# ESP_PROTO1_0.net
KiCad netlist of a schematic drawn in EAGLE
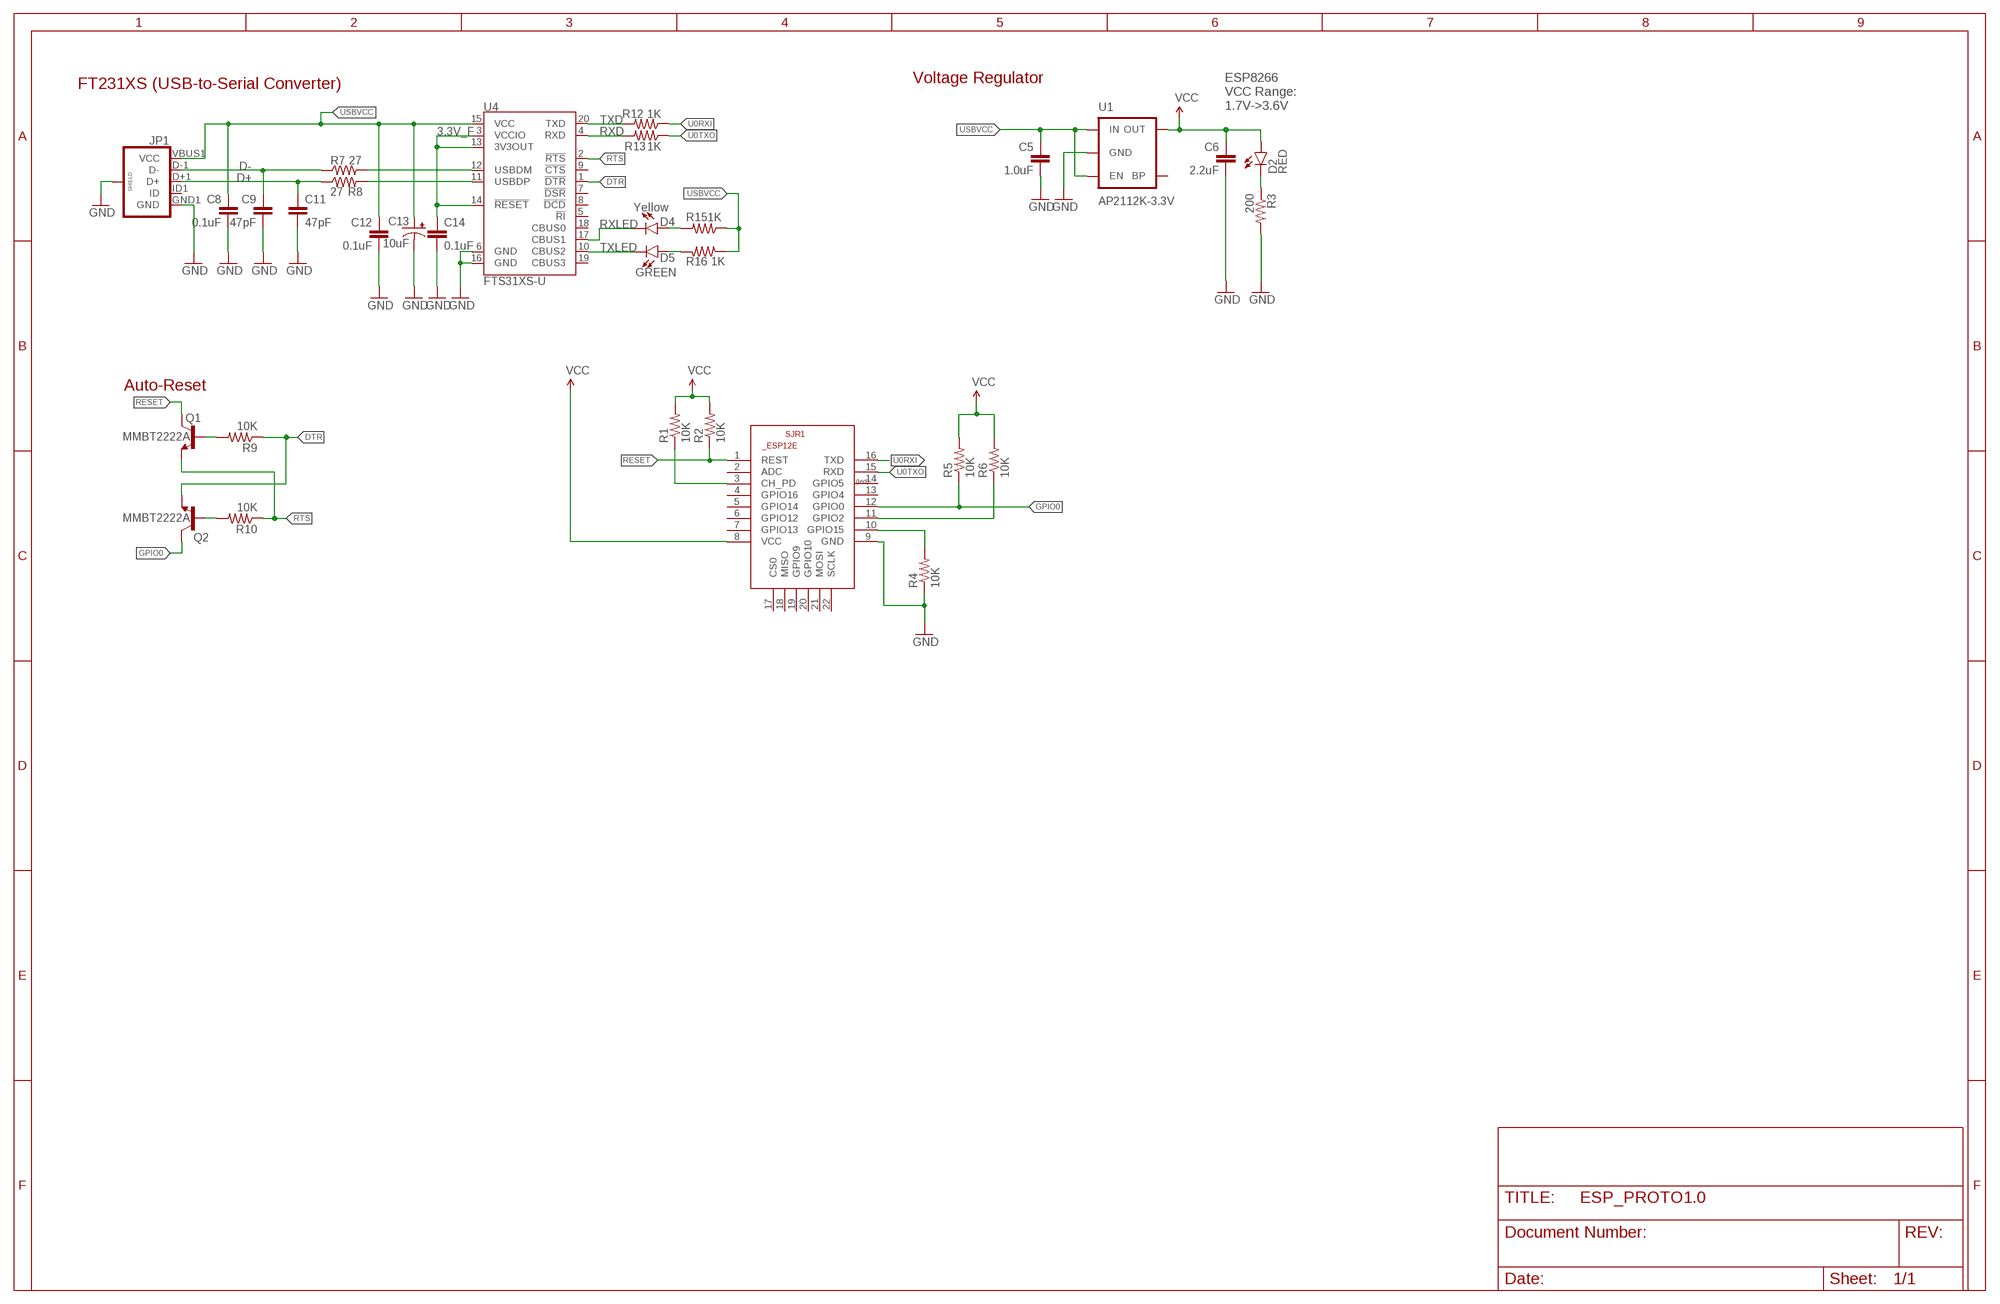
[diagram p0: schematic, sheet 1]

(export (version "E")
  (design (tool "Eeschema 10.0.6"))
  (components
    (comp (ref "C5")
      (value "1.0uF")
      (footprint "eagle-import:0805")
      (libsource (lib "eagle-import") (part "1.0UF-25V-+80/-20(0805)"))
    )
    (comp (ref "C6")
      (value "2.2uF")
      (footprint "eagle-import:0603-CAP")
      (libsource (lib "eagle-import") (part "2.2UF-10V-20%(0603)"))
    )
    (comp (ref "C8")
      (value "0.1uF")
      (footprint "eagle-import:0603-CAP")
      (libsource (lib "eagle-import") (part "0.1UF-25V(+80/-20%)(0603)"))
    )
    (comp (ref "C9")
      (value "47pF")
      (footprint "eagle-import:0603-CAP")
      (libsource (lib "eagle-import") (part "47PF-50V-5%(0603)"))
    )
    (comp (ref "C11")
      (value "47pF")
      (footprint "eagle-import:0603-CAP")
      (libsource (lib "eagle-import") (part "47PF-50V-5%(0603)"))
    )
    (comp (ref "C12")
      (value "0.1uF")
      (footprint "eagle-import:0603-CAP")
      (libsource (lib "eagle-import") (part "0.1UF-25V(+80/-20%)(0603)"))
    )
    (comp (ref "C13")
      (value "10uF")
      (footprint "eagle-import:EIA3216")
      (libsource (lib "eagle-import") (part "10UF-16V-10%(TANT)"))
    )
    (comp (ref "C14")
      (value "0.1uF")
      (footprint "eagle-import:0603-CAP")
      (libsource (lib "eagle-import") (part "0.1UF-25V(+80/-20%)(0603)"))
    )
    (comp (ref "D2")
      (value "RED")
      (footprint "eagle-import:LED-0603")
      (libsource (lib "eagle-import") (part "LED-RED0603"))
    )
    (comp (ref "D4")
      (value "Yellow")
      (footprint "eagle-import:LED-0603")
      (libsource (lib "eagle-import") (part "LED-YELLOW0603"))
    )
    (comp (ref "D5")
      (value "GREEN")
      (footprint "eagle-import:LED-0603")
      (libsource (lib "eagle-import") (part "LED-GREEN0603"))
    )
    (comp (ref "JP1")
      (value "USB_MICROB_PLUGCONN-11752")
      (footprint "eagle-import:USB-B-MICRO-SMD_V03")
      (libsource (lib "eagle-import") (part "USB_MICROB_PLUGCONN-11752"))
    )
    (comp (ref "Q1")
      (value "MMBT2222A")
      (footprint "eagle-import:SOT23-3")
      (libsource (lib "eagle-import") (part "TRANSISTOR_NPNMMBT2222A"))
    )
    (comp (ref "Q2")
      (value "MMBT2222A")
      (footprint "eagle-import:SOT23-3")
      (libsource (lib "eagle-import") (part "TRANSISTOR_NPNMMBT2222A"))
    )
    (comp (ref "R1")
      (value "10K")
      (footprint "eagle-import:0603-RES")
      (libsource (lib "eagle-import") (part "10KOHM1/10W1%(0603)0603"))
    )
    (comp (ref "R2")
      (value "10K")
      (footprint "eagle-import:0603-RES")
      (libsource (lib "eagle-import") (part "10KOHM1/10W1%(0603)0603"))
    )
    (comp (ref "R3")
      (value "200")
      (footprint "eagle-import:0603-RES")
      (libsource (lib "eagle-import") (part "200OHM1/10W1%(0603)"))
    )
    (comp (ref "R4")
      (value "10K")
      (footprint "eagle-import:0603-RES")
      (libsource (lib "eagle-import") (part "10KOHM1/10W1%(0603)0603"))
    )
    (comp (ref "R5")
      (value "10K")
      (footprint "eagle-import:0603-RES")
      (libsource (lib "eagle-import") (part "10KOHM1/10W1%(0603)0603"))
    )
    (comp (ref "R6")
      (value "10K")
      (footprint "eagle-import:0603-RES")
      (libsource (lib "eagle-import") (part "10KOHM1/10W1%(0603)0603"))
    )
    (comp (ref "R7")
      (value "27")
      (footprint "eagle-import:0603-RES")
      (libsource (lib "eagle-import") (part "27OHM1/10W1%(0603)0603-RES"))
    )
    (comp (ref "R8")
      (value "27")
      (footprint "eagle-import:0603-RES")
      (libsource (lib "eagle-import") (part "27OHM1/10W1%(0603)0603-RES"))
    )
    (comp (ref "R9")
      (value "10K")
      (footprint "eagle-import:0603-RES")
      (libsource (lib "eagle-import") (part "10KOHM1/10W1%(0603)0603"))
    )
    (comp (ref "R10")
      (value "10K")
      (footprint "eagle-import:0603-RES")
      (libsource (lib "eagle-import") (part "10KOHM1/10W1%(0603)0603"))
    )
    (comp (ref "R12")
      (value "1K")
      (footprint "eagle-import:0603-RES")
      (libsource (lib "eagle-import") (part "1KOHM-1/10W-1%(0603)"))
    )
    (comp (ref "R13")
      (value "1K")
      (footprint "eagle-import:0603-RES")
      (libsource (lib "eagle-import") (part "1KOHM-1/10W-1%(0603)"))
    )
    (comp (ref "R15")
      (value "1K")
      (footprint "eagle-import:0603-RES")
      (libsource (lib "eagle-import") (part "1KOHM-1/10W-1%(0603)"))
    )
    (comp (ref "R16")
      (value "1K")
      (footprint "eagle-import:0603-RES")
      (libsource (lib "eagle-import") (part "1KOHM-1/10W-1%(0603)"))
    )
    (comp (ref "SJR1")
      (value "ESP8266-12EESP12E")
      (footprint "eagle-import:ESP8266-ESP12E")
      (libsource (lib "eagle-import") (part "ESP8266-12EESP12E"))
    )
    (comp (ref "U1")
      (value "AP2112K-3.3V")
      (footprint "eagle-import:SOT23-5")
      (libsource (lib "eagle-import") (part "V_REG_LDOSMD"))
    )
    (comp (ref "U4")
      (value "FTS31XS-U")
      (footprint "eagle-import:SSOP20_L")
      (libsource (lib "eagle-import") (part "FT231XS"))
    )
  )
  (nets
    (net (code "1") (name "/3.3V_F") (class "Default")
      (node (ref "C14") (pin "1") (pinfunction "1_1") (pintype "passive"))
      (node (ref "U4") (pin "13") (pinfunction "3V3OUT_13") (pintype "bidirectional"))
      (node (ref "U4") (pin "14") (pinfunction "~{RESET}_14") (pintype "bidirectional"))
      (node (ref "U4") (pin "3") (pinfunction "VCCIO_3") (pintype "bidirectional"))
    )
    (net (code "2") (name "/D+") (class "Default")
      (node (ref "C11") (pin "1") (pinfunction "1_1") (pintype "passive"))
      (node (ref "JP1") (pin "D+1") (pinfunction "D+_D+1") (pintype "bidirectional"))
      (node (ref "R8") (pin "1") (pinfunction "1_1") (pintype "passive"))
    )
    (net (code "3") (name "/D-") (class "Default")
      (node (ref "C9") (pin "1") (pinfunction "1_1") (pintype "passive"))
      (node (ref "JP1") (pin "D-1") (pinfunction "D-_D-1") (pintype "bidirectional"))
      (node (ref "R7") (pin "1") (pinfunction "1_1") (pintype "passive"))
    )
    (net (code "4") (name "/RXD") (class "Default")
      (node (ref "R13") (pin "2") (pinfunction "2_2") (pintype "passive"))
      (node (ref "U4") (pin "4") (pinfunction "RXD_4") (pintype "bidirectional"))
    )
    (net (code "5") (name "/RXLED") (class "Default")
      (node (ref "D4") (pin "C") (pinfunction "C_C") (pintype "passive"))
      (node (ref "U4") (pin "17") (pinfunction "CBUS1_17") (pintype "bidirectional"))
    )
    (net (code "6") (name "/TXD") (class "Default")
      (node (ref "R12") (pin "2") (pinfunction "2_2") (pintype "passive"))
      (node (ref "U4") (pin "20") (pinfunction "TXD_20") (pintype "bidirectional"))
    )
    (net (code "7") (name "/TXLED") (class "Default")
      (node (ref "D5") (pin "C") (pinfunction "C_C") (pintype "passive"))
      (node (ref "U4") (pin "10") (pinfunction "CBUS2_10") (pintype "bidirectional"))
    )
    (net (code "8") (name "DTR") (class "Default")
      (node (ref "Q2") (pin "2") (pinfunction "E_2") (pintype "passive"))
      (node (ref "R9") (pin "1") (pinfunction "1_1") (pintype "passive"))
      (node (ref "U4") (pin "1") (pinfunction "~{DTR}_1") (pintype "bidirectional"))
    )
    (net (code "9") (name "GND") (class "Default")
      (node (ref "C11") (pin "2") (pinfunction "2_2") (pintype "passive"))
      (node (ref "C12") (pin "2") (pinfunction "2_2") (pintype "passive"))
      (node (ref "C13") (pin "C") (pinfunction "-_C") (pintype "passive"))
      (node (ref "C14") (pin "2") (pinfunction "2_2") (pintype "passive"))
      (node (ref "C5") (pin "2") (pinfunction "2_2") (pintype "passive"))
      (node (ref "C6") (pin "2") (pinfunction "2_2") (pintype "passive"))
      (node (ref "C8") (pin "2") (pinfunction "2_2") (pintype "passive"))
      (node (ref "C9") (pin "2") (pinfunction "2_2") (pintype "passive"))
      (node (ref "JP1") (pin "GND1") (pinfunction "GND_GND1") (pintype "bidirectional"))
      (node (ref "JP1") (pin "SHIELD1") (pinfunction "SHIELD_SHIELD1") (pintype "bidirectional"))
      (node (ref "JP1") (pin "SHIELD2") (pinfunction "SHIELD_SHIELD2") (pintype "bidirectional"))
      (node (ref "JP1") (pin "SHIELD3") (pinfunction "SHIELD_SHIELD3") (pintype "bidirectional"))
      (node (ref "R3") (pin "2") (pinfunction "2_2") (pintype "passive"))
      (node (ref "R4") (pin "1") (pinfunction "1_1") (pintype "passive"))
      (node (ref "SJR1") (pin "9") (pinfunction "GND_9") (pintype "bidirectional"))
      (node (ref "U1") (pin "2") (pinfunction "GND_2") (pintype "input"))
      (node (ref "U4") (pin "16") (pinfunction "GND_16") (pintype "bidirectional"))
      (node (ref "U4") (pin "6") (pinfunction "GND_6") (pintype "bidirectional"))
    )
    (net (code "10") (name "GPIO0") (class "Default")
      (node (ref "Q2") (pin "3") (pinfunction "C_3") (pintype "passive"))
      (node (ref "R5") (pin "1") (pinfunction "1_1") (pintype "passive"))
      (node (ref "SJR1") (pin "12") (pinfunction "GPIO0_12") (pintype "bidirectional"))
    )
    (net (code "11") (name "Net-(D2-PadC)") (class "Default")
      (node (ref "D2") (pin "C") (pinfunction "C_C") (pintype "passive"))
      (node (ref "R3") (pin "1") (pinfunction "1_1") (pintype "passive"))
    )
    (net (code "12") (name "Net-(D4-PadA)") (class "Default")
      (node (ref "D4") (pin "A") (pinfunction "A_A") (pintype "passive"))
      (node (ref "R15") (pin "2") (pinfunction "2_2") (pintype "passive"))
    )
    (net (code "13") (name "Net-(D5-PadA)") (class "Default")
      (node (ref "D5") (pin "A") (pinfunction "A_A") (pintype "passive"))
      (node (ref "R16") (pin "2") (pinfunction "2_2") (pintype "passive"))
    )
    (net (code "14") (name "Net-(Q1-B)") (class "Default")
      (node (ref "Q1") (pin "1") (pinfunction "B_1") (pintype "passive"))
      (node (ref "R9") (pin "2") (pinfunction "2_2") (pintype "passive"))
    )
    (net (code "15") (name "Net-(Q2-B)") (class "Default")
      (node (ref "Q2") (pin "1") (pinfunction "B_1") (pintype "passive"))
      (node (ref "R10") (pin "2") (pinfunction "2_2") (pintype "passive"))
    )
    (net (code "16") (name "Net-(SJR1-CH_PD)") (class "Default")
      (node (ref "R1") (pin "1") (pinfunction "1_1") (pintype "passive"))
      (node (ref "SJR1") (pin "3") (pinfunction "CH_PD_3") (pintype "bidirectional"))
    )
    (net (code "17") (name "Net-(SJR1-GPIO2)") (class "Default")
      (node (ref "R6") (pin "1") (pinfunction "1_1") (pintype "passive"))
      (node (ref "SJR1") (pin "11") (pinfunction "GPIO2_11") (pintype "bidirectional"))
    )
    (net (code "18") (name "Net-(SJR1-GPIO15)") (class "Default")
      (node (ref "R4") (pin "2") (pinfunction "2_2") (pintype "passive"))
      (node (ref "SJR1") (pin "10") (pinfunction "GPIO15_10") (pintype "bidirectional"))
    )
    (net (code "19") (name "Net-(U4-USBDM)") (class "Default")
      (node (ref "R7") (pin "2") (pinfunction "2_2") (pintype "passive"))
      (node (ref "U4") (pin "12") (pinfunction "USBDM_12") (pintype "bidirectional"))
    )
    (net (code "20") (name "Net-(U4-USBDP)") (class "Default")
      (node (ref "R8") (pin "2") (pinfunction "2_2") (pintype "passive"))
      (node (ref "U4") (pin "11") (pinfunction "USBDP_11") (pintype "bidirectional"))
    )
    (net (code "21") (name "RESET") (class "Default")
      (node (ref "Q1") (pin "3") (pinfunction "C_3") (pintype "passive"))
      (node (ref "R2") (pin "1") (pinfunction "1_1") (pintype "passive"))
      (node (ref "SJR1") (pin "1") (pinfunction "REST_1") (pintype "bidirectional"))
    )
    (net (code "22") (name "RTS") (class "Default")
      (node (ref "Q1") (pin "2") (pinfunction "E_2") (pintype "passive"))
      (node (ref "R10") (pin "1") (pinfunction "1_1") (pintype "passive"))
      (node (ref "U4") (pin "2") (pinfunction "~{RTS}_2") (pintype "bidirectional"))
    )
    (net (code "23") (name "U0RXI") (class "Default")
      (node (ref "R12") (pin "1") (pinfunction "1_1") (pintype "passive"))
      (node (ref "SJR1") (pin "16") (pinfunction "TXD_16") (pintype "bidirectional"))
    )
    (net (code "24") (name "U0TXO") (class "Default")
      (node (ref "R13") (pin "1") (pinfunction "1_1") (pintype "passive"))
      (node (ref "SJR1") (pin "15") (pinfunction "RXD_15") (pintype "bidirectional"))
    )
    (net (code "25") (name "USBVCC") (class "Default")
      (node (ref "C12") (pin "1") (pinfunction "1_1") (pintype "passive"))
      (node (ref "C13") (pin "A") (pinfunction "+_A") (pintype "passive"))
      (node (ref "C5") (pin "1") (pinfunction "1_1") (pintype "passive"))
      (node (ref "C8") (pin "1") (pinfunction "1_1") (pintype "passive"))
      (node (ref "JP1") (pin "VBUS1") (pinfunction "VCC_VBUS1") (pintype "bidirectional"))
      (node (ref "R15") (pin "1") (pinfunction "1_1") (pintype "passive"))
      (node (ref "R16") (pin "1") (pinfunction "1_1") (pintype "passive"))
      (node (ref "U1") (pin "1") (pinfunction "IN_1") (pintype "input"))
      (node (ref "U1") (pin "3") (pinfunction "EN_3") (pintype "input"))
      (node (ref "U4") (pin "15") (pinfunction "VCC_15") (pintype "bidirectional"))
    )
    (net (code "26") (name "VCC") (class "Default")
      (node (ref "C6") (pin "1") (pinfunction "1_1") (pintype "passive"))
      (node (ref "D2") (pin "A") (pinfunction "A_A") (pintype "passive"))
      (node (ref "R1") (pin "2") (pinfunction "2_2") (pintype "passive"))
      (node (ref "R2") (pin "2") (pinfunction "2_2") (pintype "passive"))
      (node (ref "R5") (pin "2") (pinfunction "2_2") (pintype "passive"))
      (node (ref "R6") (pin "2") (pinfunction "2_2") (pintype "passive"))
      (node (ref "SJR1") (pin "8") (pinfunction "VCC_8") (pintype "bidirectional"))
      (node (ref "U1") (pin "5") (pinfunction "OUT_5") (pintype "passive"))
    )
    (net (code "27") (name "unconnected-(JP1-ID-PadID1)") (class "Default")
      (node (ref "JP1") (pin "ID1") (pinfunction "ID_ID1") (pintype "bidirectional"))
    )
    (net (code "28") (name "unconnected-(SJR1-ADC-Pad2)") (class "Default")
      (node (ref "SJR1") (pin "2") (pinfunction "ADC_2") (pintype "bidirectional"))
    )
    (net (code "29") (name "unconnected-(SJR1-CS0-Pad17)") (class "Default")
      (node (ref "SJR1") (pin "17") (pinfunction "CS0_17") (pintype "bidirectional"))
    )
    (net (code "30") (name "unconnected-(SJR1-GPIO4-Pad13)") (class "Default")
      (node (ref "SJR1") (pin "13") (pinfunction "GPIO4_13") (pintype "bidirectional"))
    )
    (net (code "31") (name "unconnected-(SJR1-GPIO5-Pad14)") (class "Default")
      (node (ref "SJR1") (pin "14") (pinfunction "GPIO5_14") (pintype "bidirectional"))
    )
    (net (code "32") (name "unconnected-(SJR1-GPIO9-Pad19)") (class "Default")
      (node (ref "SJR1") (pin "19") (pinfunction "GPIO9_19") (pintype "bidirectional"))
    )
    (net (code "33") (name "unconnected-(SJR1-GPIO10-Pad20)") (class "Default")
      (node (ref "SJR1") (pin "20") (pinfunction "GPIO10_20") (pintype "bidirectional"))
    )
    (net (code "34") (name "unconnected-(SJR1-GPIO12-Pad6)") (class "Default")
      (node (ref "SJR1") (pin "6") (pinfunction "GPIO12_6") (pintype "bidirectional"))
    )
    (net (code "35") (name "unconnected-(SJR1-GPIO13-Pad7)") (class "Default")
      (node (ref "SJR1") (pin "7") (pinfunction "GPIO13_7") (pintype "bidirectional"))
    )
    (net (code "36") (name "unconnected-(SJR1-GPIO14-Pad5)") (class "Default")
      (node (ref "SJR1") (pin "5") (pinfunction "GPIO14_5") (pintype "bidirectional"))
    )
    (net (code "37") (name "unconnected-(SJR1-GPIO16-Pad4)") (class "Default")
      (node (ref "SJR1") (pin "4") (pinfunction "GPIO16_4") (pintype "bidirectional"))
    )
    (net (code "38") (name "unconnected-(SJR1-MISO-Pad18)") (class "Default")
      (node (ref "SJR1") (pin "18") (pinfunction "MISO_18") (pintype "bidirectional"))
    )
    (net (code "39") (name "unconnected-(SJR1-MOSI-Pad21)") (class "Default")
      (node (ref "SJR1") (pin "21") (pinfunction "MOSI_21") (pintype "bidirectional"))
    )
    (net (code "40") (name "unconnected-(SJR1-SCLK-Pad22)") (class "Default")
      (node (ref "SJR1") (pin "22") (pinfunction "SCLK_22") (pintype "bidirectional"))
    )
    (net (code "41") (name "unconnected-(U1-BP-Pad4)") (class "Default")
      (node (ref "U1") (pin "4") (pinfunction "BP_4") (pintype "input"))
    )
    (net (code "42") (name "unconnected-(U4-CBUS0-Pad18)") (class "Default")
      (node (ref "U4") (pin "18") (pinfunction "CBUS0_18") (pintype "bidirectional"))
    )
    (net (code "43") (name "unconnected-(U4-CBUS3-Pad19)") (class "Default")
      (node (ref "U4") (pin "19") (pinfunction "CBUS3_19") (pintype "bidirectional"))
    )
    (net (code "44") (name "unconnected-(U4-~{CTS}-Pad9)") (class "Default")
      (node (ref "U4") (pin "9") (pinfunction "~{CTS}_9") (pintype "bidirectional"))
    )
    (net (code "45") (name "unconnected-(U4-~{DCD}-Pad8)") (class "Default")
      (node (ref "U4") (pin "8") (pinfunction "~{DCD}_8") (pintype "bidirectional"))
    )
    (net (code "46") (name "unconnected-(U4-~{DSR}-Pad7)") (class "Default")
      (node (ref "U4") (pin "7") (pinfunction "~{DSR}_7") (pintype "bidirectional"))
    )
    (net (code "47") (name "unconnected-(U4-~{RI}-Pad5)") (class "Default")
      (node (ref "U4") (pin "5") (pinfunction "~{RI}_5") (pintype "bidirectional"))
    )
  )
)
